# 4_Outputs.net
KiCad netlist of a schematic drawn in Altium Designer
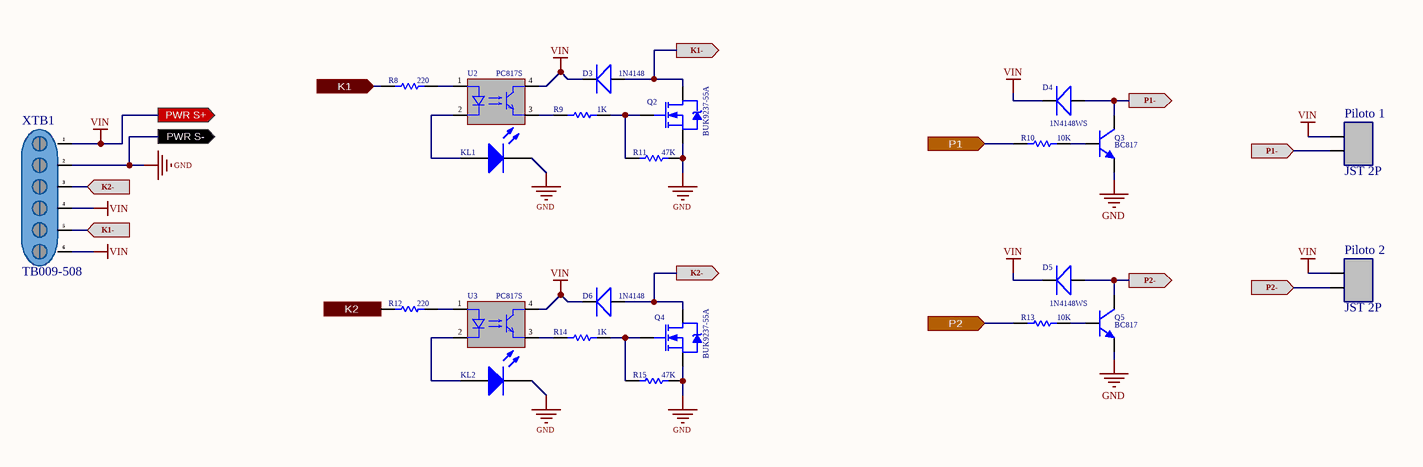
[diagram p0: 4. Outputs.SchDoc]

(export (version "E")
  (design (tool "Eeschema 10.0.6"))
  (components
    (comp (ref "D3")
      (value "1N4148")
      (footprint "Diodo DO-35")
      (description "Diodo Rectificador Recuperacion Rapida TH")
      (libsource (lib "Mi Libreria") (part "1N4148-TH"))
    )
    (comp (ref "D4")
      (value "1N4148WS")
      (footprint "SOD-323")
      (description "Diodo Rectificador Recuperacion Rapida")
      (libsource (lib "Mi Libreria") (part "1N4148WS"))
    )
    (comp (ref "D5")
      (value "1N4148WS")
      (footprint "SOD-323")
      (description "Diodo Rectificador Recuperacion Rapida")
      (libsource (lib "Mi Libreria") (part "1N4148WS"))
    )
    (comp (ref "D6")
      (value "1N4148")
      (footprint "Diodo DO-35")
      (description "Diodo Rectificador Recuperacion Rapida TH")
      (libsource (lib "Mi Libreria") (part "1N4148-TH"))
    )
    (comp (ref "KL1")
      (value "LED 0805")
      (footprint "Led 0805 Y")
      (description "LED SMD 0805")
      (libsource (lib "Led & Displays") (part "LED 0805"))
    )
    (comp (ref "KL2")
      (value "LED 0805")
      (footprint "Led 0805 Y")
      (description "LED SMD 0805")
      (libsource (lib "Led & Displays") (part "LED 0805"))
    )
    (comp (ref "Piloto 1")
      (value "JST 2P")
      (footprint "JST 2P 2.54mm")
      (description "JST 2P 2.54mm")
      (libsource (lib "Connectores GAM") (part "JST 2P 2.54mm"))
    )
    (comp (ref "Piloto 2")
      (value "JST 2P")
      (footprint "JST 2P 2.54mm")
      (description "JST 2P 2.54mm")
      (libsource (lib "Connectores GAM") (part "JST 2P 2.54mm"))
    )
    (comp (ref "Q2")
      (value "BUK9237-55A")
      (footprint "DPAK-P")
      (description "N-MOSFET DPAK")
      (libsource (lib "Mi Libreria") (part "IRFR3707Z"))
    )
    (comp (ref "Q3")
      (value "BC817")
      (footprint "SOT23127P600-8N")
      (description "BJT SOT23 NPN TRANSISTOR")
      (libsource (lib "Mi Libreria") (part "MBT2222A"))
    )
    (comp (ref "Q4")
      (value "BUK9237-55A")
      (footprint "DPAK-P")
      (description "N-MOSFET DPAK")
      (libsource (lib "Mi Libreria") (part "IRFR3707Z"))
    )
    (comp (ref "Q5")
      (value "BC817")
      (footprint "SOT23127P600-8N")
      (description "BJT SOT23 NPN TRANSISTOR")
      (libsource (lib "Mi Libreria") (part "MBT2222A"))
    )
    (comp (ref "R8")
      (value "220")
      (footprint "Resistencia 0805")
      (description "Resistencia SMD 0805")
      (libsource (lib "Mi Libreria") (part "Resistencia SMD 0805"))
    )
    (comp (ref "R9")
      (value "1K")
      (footprint "Resistencia 1206")
      (description "Resistencia SMD 1206")
      (libsource (lib "Mi Libreria") (part "Resistencia SMD 1206"))
    )
    (comp (ref "R10")
      (value "10K")
      (footprint "Resistencia 0805")
      (description "Resistencia SMD 0805")
      (libsource (lib "Mi Libreria") (part "Resistencia SMD 0805"))
    )
    (comp (ref "R11")
      (value "47K")
      (footprint "Resistencia 1206")
      (description "Resistencia SMD 1206")
      (libsource (lib "Mi Libreria") (part "Resistencia SMD 1206"))
    )
    (comp (ref "R12")
      (value "220")
      (footprint "Resistencia 0805")
      (description "Resistencia SMD 0805")
      (libsource (lib "Mi Libreria") (part "Resistencia SMD 0805"))
    )
    (comp (ref "R13")
      (value "10K")
      (footprint "Resistencia 0805")
      (description "Resistencia SMD 0805")
      (libsource (lib "Mi Libreria") (part "Resistencia SMD 0805"))
    )
    (comp (ref "R14")
      (value "1K")
      (footprint "Resistencia 1206")
      (description "Resistencia SMD 1206")
      (libsource (lib "Mi Libreria") (part "Resistencia SMD 1206"))
    )
    (comp (ref "R15")
      (value "47K")
      (footprint "Resistencia 1206")
      (description "Resistencia SMD 1206")
      (libsource (lib "Mi Libreria") (part "Resistencia SMD 1206"))
    )
    (comp (ref "U2")
      (value "PC817S")
      (footprint "SOIC 4PIN")
      (description "Optoacoplador NPN 4 PIN SMD")
      (libsource (lib "ICs") (part "PC817S"))
    )
    (comp (ref "U3")
      (value "PC817S")
      (footprint "SOIC 4PIN")
      (description "Optoacoplador NPN 4 PIN SMD")
      (libsource (lib "ICs") (part "PC817S"))
    )
    (comp (ref "XTB1")
      (value "TB009-508")
      (footprint "T-BLOCK EURO 6P 5.08MM")
      (description "Terminal de Bloque 6P 5.08mm High Current Euro Style TB009-508 CUI Devices")
      (libsource (lib "Connectores GAM") (part "T-Block E 5.08mm 6P"))
    )
  )
  (nets
    (net (code "1") (name "/K1") (class "Default")
      (node (ref "R8") (pin "1") (pinfunction "A_1") (pintype "passive"))
    )
    (net (code "2") (name "/K1-") (class "Default")
      (node (ref "D3") (pin "1") (pinfunction "A_1") (pintype "passive"))
      (node (ref "Q2") (pin "2") (pinfunction "D_2") (pintype "passive"))
      (node (ref "XTB1") (pin "5") (pinfunction "5_5") (pintype "passive"))
    )
    (net (code "3") (name "/K2") (class "Default")
      (node (ref "R12") (pin "1") (pinfunction "A_1") (pintype "passive"))
    )
    (net (code "4") (name "/K2-") (class "Default")
      (node (ref "D6") (pin "1") (pinfunction "A_1") (pintype "passive"))
      (node (ref "Q4") (pin "2") (pinfunction "D_2") (pintype "passive"))
      (node (ref "XTB1") (pin "3") (pinfunction "3_3") (pintype "passive"))
    )
    (net (code "5") (name "/P1") (class "Default")
      (node (ref "R10") (pin "1") (pinfunction "A_1") (pintype "passive"))
    )
    (net (code "6") (name "/P1-") (class "Default")
      (node (ref "D4") (pin "1") (pinfunction "A_1") (pintype "passive"))
      (node (ref "Piloto 1") (pin "2") (pinfunction "2_2") (pintype "passive"))
      (node (ref "Q3") (pin "3") (pinfunction "C_3") (pintype "passive"))
    )
    (net (code "7") (name "/P2") (class "Default")
      (node (ref "R13") (pin "1") (pinfunction "A_1") (pintype "passive"))
    )
    (net (code "8") (name "/P2-") (class "Default")
      (node (ref "D5") (pin "1") (pinfunction "A_1") (pintype "passive"))
      (node (ref "Piloto 2") (pin "2") (pinfunction "2_2") (pintype "passive"))
      (node (ref "Q5") (pin "3") (pinfunction "C_3") (pintype "passive"))
    )
    (net (code "9") (name "GND") (class "Default")
      (node (ref "KL1") (pin "2") (pinfunction "K_2") (pintype "passive"))
      (node (ref "KL2") (pin "2") (pinfunction "K_2") (pintype "passive"))
      (node (ref "Q2") (pin "3") (pinfunction "S_3") (pintype "passive"))
      (node (ref "Q3") (pin "2") (pinfunction "E_2") (pintype "passive"))
      (node (ref "Q4") (pin "3") (pinfunction "S_3") (pintype "passive"))
      (node (ref "Q5") (pin "2") (pinfunction "E_2") (pintype "passive"))
      (node (ref "R11") (pin "2") (pinfunction "B_2") (pintype "passive"))
      (node (ref "R15") (pin "2") (pinfunction "B_2") (pintype "passive"))
      (node (ref "XTB1") (pin "2") (pinfunction "2_2") (pintype "passive"))
    )
    (net (code "10") (name "Net-(KL1-A)") (class "Default")
      (node (ref "KL1") (pin "1") (pinfunction "A_1") (pintype "passive"))
      (node (ref "U2") (pin "2") (pinfunction "K_2") (pintype "passive"))
    )
    (net (code "11") (name "Net-(KL2-A)") (class "Default")
      (node (ref "KL2") (pin "1") (pinfunction "A_1") (pintype "passive"))
      (node (ref "U3") (pin "2") (pinfunction "K_2") (pintype "passive"))
    )
    (net (code "12") (name "Net-(Q2-G)") (class "Default")
      (node (ref "Q2") (pin "1") (pinfunction "G_1") (pintype "passive"))
      (node (ref "R11") (pin "1") (pinfunction "A_1") (pintype "passive"))
      (node (ref "R9") (pin "1") (pinfunction "A_1") (pintype "passive"))
    )
    (net (code "13") (name "Net-(Q3-B)") (class "Default")
      (node (ref "Q3") (pin "1") (pinfunction "B_1") (pintype "passive"))
      (node (ref "R10") (pin "2") (pinfunction "B_2") (pintype "passive"))
    )
    (net (code "14") (name "Net-(Q4-G)") (class "Default")
      (node (ref "Q4") (pin "1") (pinfunction "G_1") (pintype "passive"))
      (node (ref "R14") (pin "1") (pinfunction "A_1") (pintype "passive"))
      (node (ref "R15") (pin "1") (pinfunction "A_1") (pintype "passive"))
    )
    (net (code "15") (name "Net-(Q5-B)") (class "Default")
      (node (ref "Q5") (pin "1") (pinfunction "B_1") (pintype "passive"))
      (node (ref "R13") (pin "2") (pinfunction "B_2") (pintype "passive"))
    )
    (net (code "16") (name "Net-(R8-B)") (class "Default")
      (node (ref "R8") (pin "2") (pinfunction "B_2") (pintype "passive"))
      (node (ref "U2") (pin "1") (pinfunction "A_1") (pintype "passive"))
    )
    (net (code "17") (name "Net-(R9-B)") (class "Default")
      (node (ref "R9") (pin "2") (pinfunction "B_2") (pintype "passive"))
      (node (ref "U2") (pin "3") (pinfunction "E_3") (pintype "passive"))
    )
    (net (code "18") (name "Net-(R12-B)") (class "Default")
      (node (ref "R12") (pin "2") (pinfunction "B_2") (pintype "passive"))
      (node (ref "U3") (pin "1") (pinfunction "A_1") (pintype "passive"))
    )
    (net (code "19") (name "Net-(R14-B)") (class "Default")
      (node (ref "R14") (pin "2") (pinfunction "B_2") (pintype "passive"))
      (node (ref "U3") (pin "3") (pinfunction "E_3") (pintype "passive"))
    )
    (net (code "20") (name "VIN") (class "Default")
      (node (ref "D3") (pin "2") (pinfunction "C_2") (pintype "passive"))
      (node (ref "D4") (pin "2") (pinfunction "C_2") (pintype "passive"))
      (node (ref "D5") (pin "2") (pinfunction "C_2") (pintype "passive"))
      (node (ref "D6") (pin "2") (pinfunction "C_2") (pintype "passive"))
      (node (ref "Piloto 1") (pin "1") (pinfunction "1_1") (pintype "passive"))
      (node (ref "Piloto 2") (pin "1") (pinfunction "1_1") (pintype "passive"))
      (node (ref "U2") (pin "4") (pinfunction "C_4") (pintype "passive"))
      (node (ref "U3") (pin "4") (pinfunction "C_4") (pintype "passive"))
      (node (ref "XTB1") (pin "1") (pinfunction "1_1") (pintype "passive"))
      (node (ref "XTB1") (pin "4") (pinfunction "4_4") (pintype "passive"))
      (node (ref "XTB1") (pin "6") (pinfunction "6_6") (pintype "passive"))
    )
  )
)
